# untitled.net
KiCad netlist of a schematic drawn in EAGLE
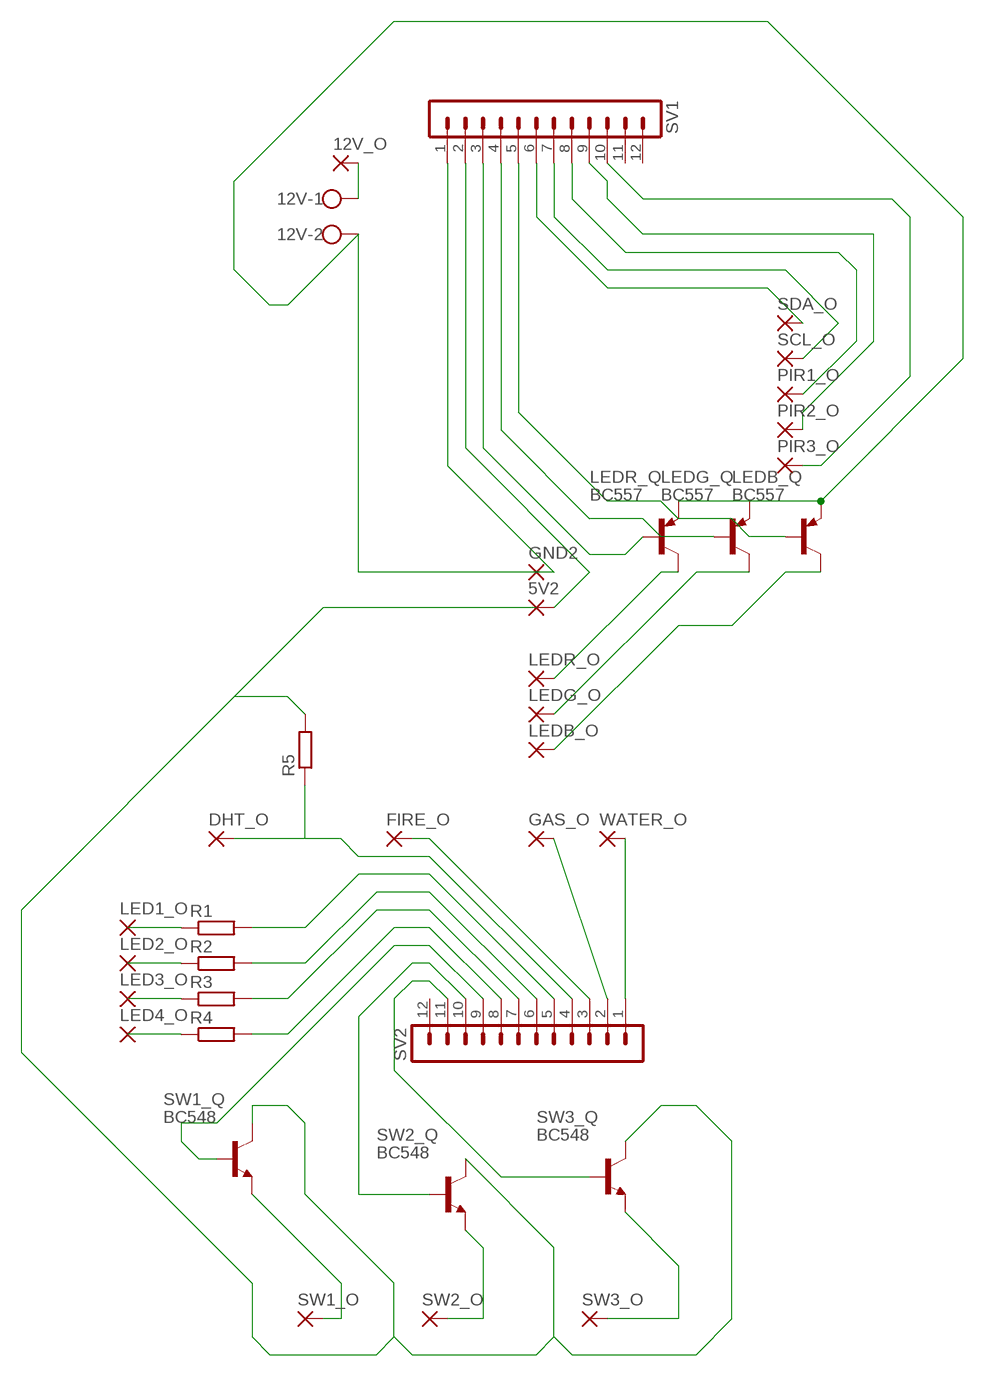
[diagram p0: schematic, sheet 1]

(export (version "E")
  (design (tool "Eeschema 10.0.6"))
  (components
    (comp (ref "5V2")
      (value "1,6/0,8")
      (footprint "eagle-import:1,6_0,8")
      (libsource (lib "eagle-import") (part "1,6/0,8"))
    )
    (comp (ref "12V")
      (value "W237-102")
      (footprint "eagle-import:W237-102")
      (fields (field (name "MPN") "237-102"))
      (libsource (lib "eagle-import") (part "W237-102"))
    )
    (comp (ref "12V_O")
      (value "1,6/0,8")
      (footprint "eagle-import:1,6_0,8")
      (libsource (lib "eagle-import") (part "1,6/0,8"))
    )
    (comp (ref "DHT_O")
      (value "1,6/0,8")
      (footprint "eagle-import:1,6_0,8")
      (libsource (lib "eagle-import") (part "1,6/0,8"))
    )
    (comp (ref "FIRE_O")
      (value "1,6/0,8")
      (footprint "eagle-import:1,6_0,8")
      (libsource (lib "eagle-import") (part "1,6/0,8"))
    )
    (comp (ref "GAS_O")
      (value "1,6/0,8")
      (footprint "eagle-import:1,6_0,8")
      (libsource (lib "eagle-import") (part "1,6/0,8"))
    )
    (comp (ref "GND2")
      (value "1,6/0,8")
      (footprint "eagle-import:1,6_0,8")
      (libsource (lib "eagle-import") (part "1,6/0,8"))
    )
    (comp (ref "LED1_O")
      (value "1,6/0,8")
      (footprint "eagle-import:1,6_0,8")
      (libsource (lib "eagle-import") (part "1,6/0,8"))
    )
    (comp (ref "LED2_O")
      (value "1,6/0,8")
      (footprint "eagle-import:1,6_0,8")
      (libsource (lib "eagle-import") (part "1,6/0,8"))
    )
    (comp (ref "LED3_O")
      (value "1,6/0,8")
      (footprint "eagle-import:1,6_0,8")
      (libsource (lib "eagle-import") (part "1,6/0,8"))
    )
    (comp (ref "LED4_O")
      (value "1,6/0,8")
      (footprint "eagle-import:1,6_0,8")
      (libsource (lib "eagle-import") (part "1,6/0,8"))
    )
    (comp (ref "LEDB_O")
      (value "1,6/0,8")
      (footprint "eagle-import:1,6_0,8")
      (libsource (lib "eagle-import") (part "1,6/0,8"))
    )
    (comp (ref "LEDB_Q")
      (value "BC557")
      (footprint "eagle-import:TO92-EBC")
      (libsource (lib "eagle-import") (part "BC557"))
    )
    (comp (ref "LEDG_O")
      (value "1,6/0,8")
      (footprint "eagle-import:1,6_0,8")
      (libsource (lib "eagle-import") (part "1,6/0,8"))
    )
    (comp (ref "LEDG_Q")
      (value "BC557")
      (footprint "eagle-import:TO92-EBC")
      (libsource (lib "eagle-import") (part "BC557"))
    )
    (comp (ref "LEDR_O")
      (value "1,6/0,8")
      (footprint "eagle-import:1,6_0,8")
      (libsource (lib "eagle-import") (part "1,6/0,8"))
    )
    (comp (ref "LEDR_Q")
      (value "BC557")
      (footprint "eagle-import:TO92-EBC")
      (libsource (lib "eagle-import") (part "BC557"))
    )
    (comp (ref "PIR1_O")
      (value "1,6/0,8")
      (footprint "eagle-import:1,6_0,8")
      (libsource (lib "eagle-import") (part "1,6/0,8"))
    )
    (comp (ref "PIR2_O")
      (value "1,6/0,8")
      (footprint "eagle-import:1,6_0,8")
      (libsource (lib "eagle-import") (part "1,6/0,8"))
    )
    (comp (ref "PIR3_O")
      (value "1,6/0,8")
      (footprint "eagle-import:1,6_0,8")
      (libsource (lib "eagle-import") (part "1,6/0,8"))
    )
    (comp (ref "R1")
      (value "R-EU_0207/15")
      (footprint "eagle-import:0207_15")
      (libsource (lib "eagle-import") (part "R-EU_0207/15"))
    )
    (comp (ref "R2")
      (value "R-EU_0207/15")
      (footprint "eagle-import:0207_15")
      (libsource (lib "eagle-import") (part "R-EU_0207/15"))
    )
    (comp (ref "R3")
      (value "R-EU_0207/15")
      (footprint "eagle-import:0207_15")
      (libsource (lib "eagle-import") (part "R-EU_0207/15"))
    )
    (comp (ref "R4")
      (value "R-EU_0207/15")
      (footprint "eagle-import:0207_15")
      (libsource (lib "eagle-import") (part "R-EU_0207/15"))
    )
    (comp (ref "R5")
      (value "R-EU_0207/15")
      (footprint "eagle-import:0207_15")
      (libsource (lib "eagle-import") (part "R-EU_0207/15"))
    )
    (comp (ref "SCL_O")
      (value "1,6/0,8")
      (footprint "eagle-import:1,6_0,8")
      (libsource (lib "eagle-import") (part "1,6/0,8"))
    )
    (comp (ref "SDA_O")
      (value "1,6/0,8")
      (footprint "eagle-import:1,6_0,8")
      (libsource (lib "eagle-import") (part "1,6/0,8"))
    )
    (comp (ref "SV1")
      (value "MA12-1W")
      (footprint "eagle-import:MA12-1W")
      (libsource (lib "eagle-import") (part "MA12-1W"))
    )
    (comp (ref "SV2")
      (value "MA12-1W")
      (footprint "eagle-import:MA12-1W")
      (libsource (lib "eagle-import") (part "MA12-1W"))
    )
    (comp (ref "SW1_O")
      (value "1,6/0,8")
      (footprint "eagle-import:1,6_0,8")
      (libsource (lib "eagle-import") (part "1,6/0,8"))
    )
    (comp (ref "SW1_Q")
      (value "BC548")
      (footprint "eagle-import:TO92-EBC")
      (libsource (lib "eagle-import") (part "BC548"))
    )
    (comp (ref "SW2_O")
      (value "1,6/0,8")
      (footprint "eagle-import:1,6_0,8")
      (libsource (lib "eagle-import") (part "1,6/0,8"))
    )
    (comp (ref "SW2_Q")
      (value "BC548")
      (footprint "eagle-import:TO92-EBC")
      (libsource (lib "eagle-import") (part "BC548"))
    )
    (comp (ref "SW3_O")
      (value "1,6/0,8")
      (footprint "eagle-import:1,6_0,8")
      (libsource (lib "eagle-import") (part "1,6/0,8"))
    )
    (comp (ref "SW3_Q")
      (value "BC548")
      (footprint "eagle-import:TO92-EBC")
      (libsource (lib "eagle-import") (part "BC548"))
    )
    (comp (ref "WATER_O")
      (value "1,6/0,8")
      (footprint "eagle-import:1,6_0,8")
      (libsource (lib "eagle-import") (part "1,6/0,8"))
    )
  )
  (nets
    (net (code "1") (name "Net-(5V2-P)") (class "Default")
      (node (ref "5V2") (pin "1") (pinfunction "P_1") (pintype "passive"))
      (node (ref "SV1") (pin "2") (pinfunction "2_2") (pintype "passive"))
    )
    (net (code "2") (name "Net-(12VA-KL)") (class "Default")
      (node (ref "12V") (pin "1") (pinfunction "KL_1") (pintype "passive"))
      (node (ref "12V_O") (pin "1") (pinfunction "P_1") (pintype "passive"))
    )
    (net (code "3") (name "Net-(12VB-KL)") (class "Default")
      (node (ref "12V") (pin "2") (pinfunction "KL_2") (pintype "passive"))
      (node (ref "GND2") (pin "1") (pinfunction "P_1") (pintype "passive"))
      (node (ref "LEDB_Q") (pin "E") (pinfunction "E_E") (pintype "passive"))
      (node (ref "LEDG_Q") (pin "E") (pinfunction "E_E") (pintype "passive"))
      (node (ref "LEDR_Q") (pin "E") (pinfunction "E_E") (pintype "passive"))
      (node (ref "SV1") (pin "1") (pinfunction "1_1") (pintype "passive"))
    )
    (net (code "4") (name "Net-(DHT_O-P)") (class "Default")
      (node (ref "DHT_O") (pin "1") (pinfunction "P_1") (pintype "passive"))
      (node (ref "R5") (pin "1") (pinfunction "1_1") (pintype "passive"))
      (node (ref "SV2") (pin "4") (pinfunction "4_4") (pintype "passive"))
    )
    (net (code "5") (name "Net-(FIRE_O-P)") (class "Default")
      (node (ref "FIRE_O") (pin "1") (pinfunction "P_1") (pintype "passive"))
      (node (ref "SV2") (pin "3") (pinfunction "3_3") (pintype "passive"))
    )
    (net (code "6") (name "Net-(GAS_O-P)") (class "Default")
      (node (ref "GAS_O") (pin "1") (pinfunction "P_1") (pintype "passive"))
      (node (ref "SV2") (pin "2") (pinfunction "2_2") (pintype "passive"))
    )
    (net (code "7") (name "Net-(LED1_O-P)") (class "Default")
      (node (ref "LED1_O") (pin "1") (pinfunction "P_1") (pintype "passive"))
      (node (ref "R1") (pin "1") (pinfunction "1_1") (pintype "passive"))
    )
    (net (code "8") (name "Net-(LED2_O-P)") (class "Default")
      (node (ref "LED2_O") (pin "1") (pinfunction "P_1") (pintype "passive"))
      (node (ref "R2") (pin "1") (pinfunction "1_1") (pintype "passive"))
    )
    (net (code "9") (name "Net-(LED3_O-P)") (class "Default")
      (node (ref "LED3_O") (pin "1") (pinfunction "P_1") (pintype "passive"))
      (node (ref "R3") (pin "1") (pinfunction "1_1") (pintype "passive"))
    )
    (net (code "10") (name "Net-(LED4_O-P)") (class "Default")
      (node (ref "LED4_O") (pin "1") (pinfunction "P_1") (pintype "passive"))
      (node (ref "R4") (pin "1") (pinfunction "1_1") (pintype "passive"))
    )
    (net (code "11") (name "Net-(LEDB_O-P)") (class "Default")
      (node (ref "LEDB_O") (pin "1") (pinfunction "P_1") (pintype "passive"))
      (node (ref "LEDB_Q") (pin "C") (pinfunction "C_C") (pintype "passive"))
    )
    (net (code "12") (name "Net-(LEDB_Q-PadB)") (class "Default")
      (node (ref "LEDB_Q") (pin "B") (pinfunction "B_B") (pintype "passive"))
      (node (ref "SV1") (pin "5") (pinfunction "5_5") (pintype "passive"))
    )
    (net (code "13") (name "Net-(LEDG_O-P)") (class "Default")
      (node (ref "LEDG_O") (pin "1") (pinfunction "P_1") (pintype "passive"))
      (node (ref "LEDG_Q") (pin "C") (pinfunction "C_C") (pintype "passive"))
    )
    (net (code "14") (name "Net-(LEDG_Q-PadB)") (class "Default")
      (node (ref "LEDG_Q") (pin "B") (pinfunction "B_B") (pintype "passive"))
      (node (ref "SV1") (pin "4") (pinfunction "4_4") (pintype "passive"))
    )
    (net (code "15") (name "Net-(LEDR_O-P)") (class "Default")
      (node (ref "LEDR_O") (pin "1") (pinfunction "P_1") (pintype "passive"))
      (node (ref "LEDR_Q") (pin "C") (pinfunction "C_C") (pintype "passive"))
    )
    (net (code "16") (name "Net-(LEDR_Q-PadB)") (class "Default")
      (node (ref "LEDR_Q") (pin "B") (pinfunction "B_B") (pintype "passive"))
      (node (ref "SV1") (pin "3") (pinfunction "3_3") (pintype "passive"))
    )
    (net (code "17") (name "Net-(PIR1_O-P)") (class "Default")
      (node (ref "PIR1_O") (pin "1") (pinfunction "P_1") (pintype "passive"))
      (node (ref "SV1") (pin "8") (pinfunction "8_8") (pintype "passive"))
    )
    (net (code "18") (name "Net-(PIR2_O-P)") (class "Default")
      (node (ref "PIR2_O") (pin "1") (pinfunction "P_1") (pintype "passive"))
      (node (ref "SV1") (pin "9") (pinfunction "9_9") (pintype "passive"))
    )
    (net (code "19") (name "Net-(PIR3_O-P)") (class "Default")
      (node (ref "PIR3_O") (pin "1") (pinfunction "P_1") (pintype "passive"))
      (node (ref "SV1") (pin "10") (pinfunction "10_10") (pintype "passive"))
    )
    (net (code "20") (name "Net-(R1-Pad2)") (class "Default")
      (node (ref "R1") (pin "2") (pinfunction "2_2") (pintype "passive"))
      (node (ref "SV2") (pin "5") (pinfunction "5_5") (pintype "passive"))
    )
    (net (code "21") (name "Net-(R2-Pad2)") (class "Default")
      (node (ref "R2") (pin "2") (pinfunction "2_2") (pintype "passive"))
      (node (ref "SV2") (pin "6") (pinfunction "6_6") (pintype "passive"))
    )
    (net (code "22") (name "Net-(R3-Pad2)") (class "Default")
      (node (ref "R3") (pin "2") (pinfunction "2_2") (pintype "passive"))
      (node (ref "SV2") (pin "7") (pinfunction "7_7") (pintype "passive"))
    )
    (net (code "23") (name "Net-(R4-Pad2)") (class "Default")
      (node (ref "R4") (pin "2") (pinfunction "2_2") (pintype "passive"))
      (node (ref "SV2") (pin "8") (pinfunction "8_8") (pintype "passive"))
    )
    (net (code "24") (name "Net-(R5-Pad2)") (class "Default")
      (node (ref "R5") (pin "2") (pinfunction "2_2") (pintype "passive"))
      (node (ref "SW1_Q") (pin "C") (pinfunction "C_C") (pintype "passive"))
      (node (ref "SW2_Q") (pin "C") (pinfunction "C_C") (pintype "passive"))
      (node (ref "SW3_Q") (pin "C") (pinfunction "C_C") (pintype "passive"))
    )
    (net (code "25") (name "Net-(SCL_O-P)") (class "Default")
      (node (ref "SCL_O") (pin "1") (pinfunction "P_1") (pintype "passive"))
      (node (ref "SV1") (pin "7") (pinfunction "7_7") (pintype "passive"))
    )
    (net (code "26") (name "Net-(SDA_O-P)") (class "Default")
      (node (ref "SDA_O") (pin "1") (pinfunction "P_1") (pintype "passive"))
      (node (ref "SV1") (pin "6") (pinfunction "6_6") (pintype "passive"))
    )
    (net (code "27") (name "Net-(SV2-Pad9)") (class "Default")
      (node (ref "SV2") (pin "9") (pinfunction "9_9") (pintype "passive"))
      (node (ref "SW1_Q") (pin "B") (pinfunction "B_B") (pintype "passive"))
    )
    (net (code "28") (name "Net-(SV2-Pad10)") (class "Default")
      (node (ref "SV2") (pin "10") (pinfunction "10_10") (pintype "passive"))
      (node (ref "SW2_Q") (pin "B") (pinfunction "B_B") (pintype "passive"))
    )
    (net (code "29") (name "Net-(SV2-Pad11)") (class "Default")
      (node (ref "SV2") (pin "11") (pinfunction "11_11") (pintype "passive"))
      (node (ref "SW3_Q") (pin "B") (pinfunction "B_B") (pintype "passive"))
    )
    (net (code "30") (name "Net-(SW1_O-P)") (class "Default")
      (node (ref "SW1_O") (pin "1") (pinfunction "P_1") (pintype "passive"))
      (node (ref "SW1_Q") (pin "E") (pinfunction "E_E") (pintype "passive"))
    )
    (net (code "31") (name "Net-(SW2_O-P)") (class "Default")
      (node (ref "SW2_O") (pin "1") (pinfunction "P_1") (pintype "passive"))
      (node (ref "SW2_Q") (pin "E") (pinfunction "E_E") (pintype "passive"))
    )
    (net (code "32") (name "Net-(SW3_O-P)") (class "Default")
      (node (ref "SW3_O") (pin "1") (pinfunction "P_1") (pintype "passive"))
      (node (ref "SW3_Q") (pin "E") (pinfunction "E_E") (pintype "passive"))
    )
    (net (code "33") (name "Net-(WATER_O-P)") (class "Default")
      (node (ref "SV2") (pin "1") (pinfunction "1_1") (pintype "passive"))
      (node (ref "WATER_O") (pin "1") (pinfunction "P_1") (pintype "passive"))
    )
    (net (code "34") (name "unconnected-(SV1-Pad11)") (class "Default")
      (node (ref "SV1") (pin "11") (pinfunction "11_11") (pintype "passive"))
    )
    (net (code "35") (name "unconnected-(SV1-Pad12)") (class "Default")
      (node (ref "SV1") (pin "12") (pinfunction "12_12") (pintype "passive"))
    )
    (net (code "36") (name "unconnected-(SV2-Pad12)") (class "Default")
      (node (ref "SV2") (pin "12") (pinfunction "12_12") (pintype "passive"))
    )
  )
)
